# design.net
KiCad netlist of a schematic drawn in Altium Designer
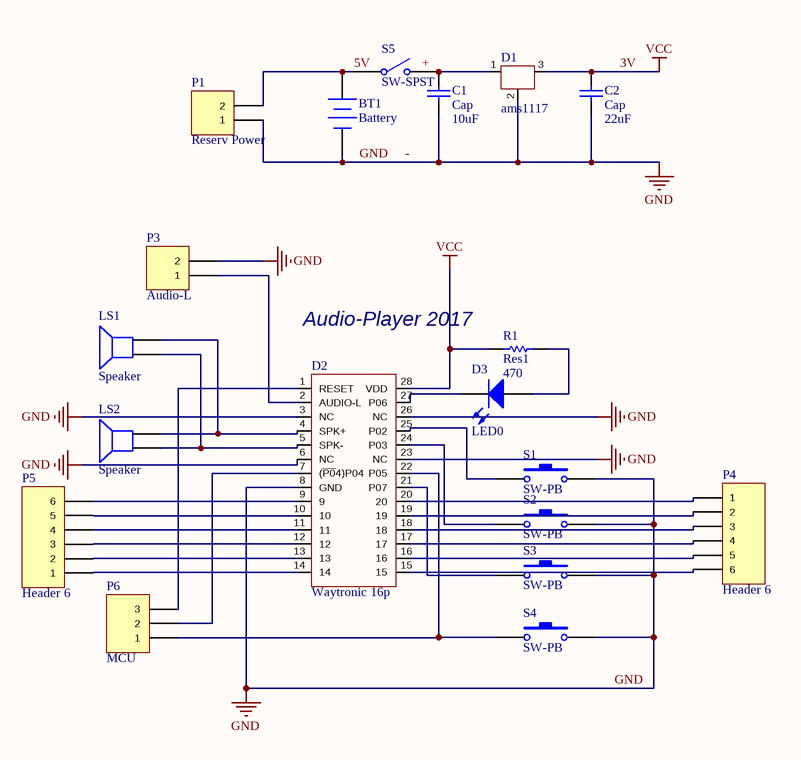
[diagram p0: Схема электрическая.SchDoc]

(export (version "E")
  (design (tool "Eeschema 10.0.6"))
  (components
    (comp (ref "BT1")
      (value "Battery")
      (footprint "BAT-2")
      (description "Multicell Battery")
      (fields (field (name "PUBLISHER") "Altium Limited"))
      (libsource (lib "Miscellaneous Devices") (part "Battery"))
    )
    (comp (ref "C1")
      (value "Cap")
      (footprint "RAD-0.3")
      (description "Capacitor")
      (fields (field (name "ALTIUM_VALUE") "10uF") (field (name "PUBLISHER") "Altium Limited"))
      (libsource (lib "Miscellaneous Devices") (part "Cap"))
    )
    (comp (ref "C2")
      (value "Cap")
      (footprint "RAD-0.3")
      (description "Capacitor")
      (fields (field (name "ALTIUM_VALUE") "22uF") (field (name "PUBLISHER") "Altium Limited"))
      (libsource (lib "Miscellaneous Devices") (part "Cap"))
    )
    (comp (ref "D1")
      (value "ams1117")
      (footprint "Библиотека компонентов:ams1117")
      (libsource (lib "Библиотека символов") (part "ams1117"))
    )
    (comp (ref "D2")
      (value "Waytronic 16p")
      (footprint "Библиотека компонентов:Waytronic_16p")
      (libsource (lib "Библиотека символов") (part "Waytronic 16p"))
    )
    (comp (ref "D3")
      (value "LED0")
      (footprint "LED-0")
      (description "Typical INFRARED GaAs LED")
      (fields (field (name "PUBLISHER") "Altium Limited"))
      (libsource (lib "Miscellaneous Devices") (part "LED0"))
    )
    (comp (ref "LS1")
      (value "Speaker")
      (footprint "PIN2")
      (description "Loudspeaker")
      (fields (field (name "PUBLISHER") "Altium Limited"))
      (libsource (lib "Miscellaneous Devices") (part "Speaker"))
    )
    (comp (ref "LS2")
      (value "Speaker")
      (footprint "PIN2")
      (description "Loudspeaker")
      (fields (field (name "PUBLISHER") "Altium Limited"))
      (libsource (lib "Miscellaneous Devices") (part "Speaker"))
    )
    (comp (ref "P1")
      (value "Reserv Power")
      (footprint "HDR1X2")
      (description "Header, 2-Pin")
      (fields (field (name "PUBLISHER") "Altium Limited"))
      (libsource (lib "Miscellaneous Connectors") (part "Header 2"))
    )
    (comp (ref "P3")
      (value "Audio-L")
      (footprint "HDR1X2")
      (description "Header, 2-Pin")
      (fields (field (name "PUBLISHER") "Altium Limited"))
      (libsource (lib "Miscellaneous Connectors") (part "Header 2"))
    )
    (comp (ref "P4")
      (value "Header 6")
      (footprint "HDR1X6")
      (description "Header, 6-Pin")
      (fields (field (name "PUBLISHER") "Altium Limited"))
      (libsource (lib "") (part "Header 6_1"))
    )
    (comp (ref "P5")
      (value "Header 6")
      (footprint "HDR1X6")
      (description "Header, 6-Pin")
      (fields (field (name "PUBLISHER") "Altium Limited"))
      (libsource (lib "Miscellaneous Connectors") (part "Header 6"))
    )
    (comp (ref "P6")
      (value "MCU")
      (footprint "HDR1X3H")
      (description "Header, 3-Pin, Right Angle")
      (fields (field (name "PUBLISHER") "Altium Limited"))
      (libsource (lib "Miscellaneous Connectors") (part "Header 3H"))
    )
    (comp (ref "R1")
      (value "Res1")
      (footprint "AXIAL-0.3")
      (description "Resistor")
      (fields (field (name "ALTIUM_VALUE") "470") (field (name "PUBLISHER") "Altium Limited"))
      (libsource (lib "Miscellaneous Devices") (part "Res1"))
    )
    (comp (ref "S1")
      (value "SW-PB")
      (footprint "SPST-2")
      (description "Switch")
      (fields (field (name "PUBLISHER") "Altium Limited"))
      (libsource (lib "Miscellaneous Devices") (part "SW-PB"))
    )
    (comp (ref "S2")
      (value "SW-PB")
      (footprint "SPST-2")
      (description "Switch")
      (fields (field (name "PUBLISHER") "Altium Limited"))
      (libsource (lib "Miscellaneous Devices") (part "SW-PB"))
    )
    (comp (ref "S3")
      (value "SW-PB")
      (footprint "SPST-2")
      (description "Switch")
      (fields (field (name "PUBLISHER") "Altium Limited"))
      (libsource (lib "Miscellaneous Devices") (part "SW-PB"))
    )
    (comp (ref "S4")
      (value "SW-PB")
      (footprint "SPST-2")
      (description "Switch")
      (fields (field (name "PUBLISHER") "Altium Limited"))
      (libsource (lib "Miscellaneous Devices") (part "SW-PB"))
    )
    (comp (ref "S5")
      (value "SW-SPST")
      (footprint "SPST-2")
      (description "Single-Pole, Single-Throw Switch")
      (fields (field (name "PUBLISHER") "Altium Limited"))
      (libsource (lib "Miscellaneous Devices") (part "SW-SPST"))
    )
  )
  (nets
    (net (code "3") (name "GND") (class "Default")
      (node (ref "BT1") (pin "2") (pinfunction "-_2") (pintype "passive"))
      (node (ref "C1") (pin "1") (pinfunction "1_1") (pintype "passive"))
      (node (ref "C2") (pin "1") (pinfunction "1_1") (pintype "passive"))
      (node (ref "D1") (pin "2") (pinfunction "GND_2") (pintype "passive"))
      (node (ref "D2") (pin "23") (pinfunction "NC_23") (pintype "passive"))
      (node (ref "D2") (pin "26") (pinfunction "NC_26") (pintype "passive"))
      (node (ref "D2") (pin "3") (pinfunction "NC_3") (pintype "passive"))
      (node (ref "D2") (pin "6") (pinfunction "NC_6") (pintype "passive"))
      (node (ref "D2") (pin "8") (pinfunction "GND_8") (pintype "passive"))
      (node (ref "P1") (pin "1") (pinfunction "1_1") (pintype "passive"))
      (node (ref "P3") (pin "2") (pinfunction "2_2") (pintype "passive"))
      (node (ref "S1") (pin "2") (pinfunction "2_2") (pintype "passive"))
      (node (ref "S2") (pin "2") (pinfunction "2_2") (pintype "passive"))
      (node (ref "S3") (pin "2") (pinfunction "2_2") (pintype "passive"))
      (node (ref "S4") (pin "2") (pinfunction "2_2") (pintype "passive"))
    )
    (net (code "4") (name "Net-(BT1-+)") (class "Default")
      (node (ref "BT1") (pin "1") (pinfunction "+_1") (pintype "passive"))
      (node (ref "P1") (pin "2") (pinfunction "2_2") (pintype "passive"))
      (node (ref "S5") (pin "1") (pinfunction "COMMON_1") (pintype "passive"))
    )
    (net (code "5") (name "Net-(D1-Vin)") (class "Default")
      (node (ref "C1") (pin "2") (pinfunction "2_2") (pintype "passive"))
      (node (ref "D1") (pin "1") (pinfunction "Vin_1") (pintype "passive"))
      (node (ref "S5") (pin "2") (pinfunction "NO_2") (pintype "passive"))
    )
    (net (code "6") (name "Net-(D2-(~{P0}4)P04)") (class "Default")
      (node (ref "D2") (pin "7") (pinfunction "(~{P0}4)P04_7") (pintype "passive"))
      (node (ref "P6") (pin "2") (pinfunction "2_2") (pintype "passive"))
    )
    (net (code "7") (name "Net-(D2-AUDIO-L)") (class "Default")
      (node (ref "D2") (pin "2") (pinfunction "AUDIO-L_2") (pintype "passive"))
      (node (ref "P3") (pin "1") (pinfunction "1_1") (pintype "passive"))
    )
    (net (code "8") (name "Net-(D2-P02)") (class "Default")
      (node (ref "D2") (pin "25") (pinfunction "P02_25") (pintype "passive"))
      (node (ref "S1") (pin "1") (pinfunction "1_1") (pintype "passive"))
    )
    (net (code "9") (name "Net-(D2-P03)") (class "Default")
      (node (ref "D2") (pin "24") (pinfunction "P03_24") (pintype "passive"))
      (node (ref "S2") (pin "1") (pinfunction "1_1") (pintype "passive"))
    )
    (net (code "10") (name "Net-(D2-P05)") (class "Default")
      (node (ref "D2") (pin "22") (pinfunction "P05_22") (pintype "passive"))
      (node (ref "P6") (pin "1") (pinfunction "1_1") (pintype "passive"))
      (node (ref "S4") (pin "1") (pinfunction "1_1") (pintype "passive"))
    )
    (net (code "11") (name "Net-(D2-P06)") (class "Default")
      (node (ref "D2") (pin "27") (pinfunction "P06_27") (pintype "passive"))
      (node (ref "D3") (pin "2") (pinfunction "K_2") (pintype "passive"))
    )
    (net (code "12") (name "Net-(D2-P07)") (class "Default")
      (node (ref "D2") (pin "21") (pinfunction "P07_21") (pintype "passive"))
      (node (ref "S3") (pin "1") (pinfunction "1_1") (pintype "passive"))
    )
    (net (code "13") (name "Net-(D2-Pad9)") (class "Default")
      (node (ref "D2") (pin "9") (pinfunction "9_9") (pintype "passive"))
      (node (ref "P5") (pin "6") (pinfunction "6_6") (pintype "passive"))
    )
    (net (code "14") (name "Net-(D2-Pad10)") (class "Default")
      (node (ref "D2") (pin "10") (pinfunction "10_10") (pintype "passive"))
      (node (ref "P5") (pin "5") (pinfunction "5_5") (pintype "passive"))
    )
    (net (code "15") (name "Net-(D2-Pad11)") (class "Default")
      (node (ref "D2") (pin "11") (pinfunction "11_11") (pintype "passive"))
      (node (ref "P5") (pin "4") (pinfunction "4_4") (pintype "passive"))
    )
    (net (code "16") (name "Net-(D2-Pad12)") (class "Default")
      (node (ref "D2") (pin "12") (pinfunction "12_12") (pintype "passive"))
      (node (ref "P5") (pin "3") (pinfunction "3_3") (pintype "passive"))
    )
    (net (code "17") (name "Net-(D2-Pad13)") (class "Default")
      (node (ref "D2") (pin "13") (pinfunction "13_13") (pintype "passive"))
      (node (ref "P5") (pin "2") (pinfunction "2_2") (pintype "passive"))
    )
    (net (code "18") (name "Net-(D2-Pad14)") (class "Default")
      (node (ref "D2") (pin "14") (pinfunction "14_14") (pintype "passive"))
      (node (ref "P5") (pin "1") (pinfunction "1_1") (pintype "passive"))
    )
    (net (code "19") (name "Net-(D2-Pad15)") (class "Default")
      (node (ref "D2") (pin "15") (pinfunction "15_15") (pintype "passive"))
      (node (ref "P4") (pin "6") (pinfunction "6_6") (pintype "passive"))
    )
    (net (code "20") (name "Net-(D2-Pad16)") (class "Default")
      (node (ref "D2") (pin "16") (pinfunction "16_16") (pintype "passive"))
      (node (ref "P4") (pin "5") (pinfunction "5_5") (pintype "passive"))
    )
    (net (code "21") (name "Net-(D2-Pad17)") (class "Default")
      (node (ref "D2") (pin "17") (pinfunction "17_17") (pintype "passive"))
      (node (ref "P4") (pin "4") (pinfunction "4_4") (pintype "passive"))
    )
    (net (code "22") (name "Net-(D2-Pad18)") (class "Default")
      (node (ref "D2") (pin "18") (pinfunction "18_18") (pintype "passive"))
      (node (ref "P4") (pin "3") (pinfunction "3_3") (pintype "passive"))
    )
    (net (code "23") (name "Net-(D2-Pad19)") (class "Default")
      (node (ref "D2") (pin "19") (pinfunction "19_19") (pintype "passive"))
      (node (ref "P4") (pin "2") (pinfunction "2_2") (pintype "passive"))
    )
    (net (code "24") (name "Net-(D2-Pad20)") (class "Default")
      (node (ref "D2") (pin "20") (pinfunction "20_20") (pintype "passive"))
      (node (ref "P4") (pin "1") (pinfunction "1_1") (pintype "passive"))
    )
    (net (code "25") (name "Net-(D2-RESET)") (class "Default")
      (node (ref "D2") (pin "1") (pinfunction "RESET_1") (pintype "passive"))
      (node (ref "P6") (pin "3") (pinfunction "3_3") (pintype "passive"))
    )
    (net (code "26") (name "Net-(D2-SPK+)") (class "Default")
      (node (ref "D2") (pin "4") (pinfunction "SPK+_4") (pintype "passive"))
      (node (ref "LS1") (pin "2") (pinfunction "2_2") (pintype "passive"))
      (node (ref "LS2") (pin "2") (pinfunction "2_2") (pintype "passive"))
    )
    (net (code "27") (name "Net-(D2-SPK-)") (class "Default")
      (node (ref "D2") (pin "5") (pinfunction "SPK-_5") (pintype "passive"))
      (node (ref "LS1") (pin "1") (pinfunction "1_1") (pintype "passive"))
      (node (ref "LS2") (pin "1") (pinfunction "1_1") (pintype "passive"))
    )
    (net (code "28") (name "Net-(D3-A)") (class "Default")
      (node (ref "D3") (pin "1") (pinfunction "A_1") (pintype "passive"))
      (node (ref "R1") (pin "2") (pinfunction "2_2") (pintype "passive"))
    )
    (net (code "29") (name "VCC") (class "Default")
      (node (ref "C2") (pin "2") (pinfunction "2_2") (pintype "passive"))
      (node (ref "D1") (pin "3") (pinfunction "Vout_3") (pintype "passive"))
      (node (ref "D2") (pin "28") (pinfunction "VDD_28") (pintype "passive"))
      (node (ref "R1") (pin "1") (pinfunction "1_1") (pintype "passive"))
    )
  )
)
